# JLink_ARM-OB_Sch.net
KiCad netlist of a schematic drawn in Altium Designer
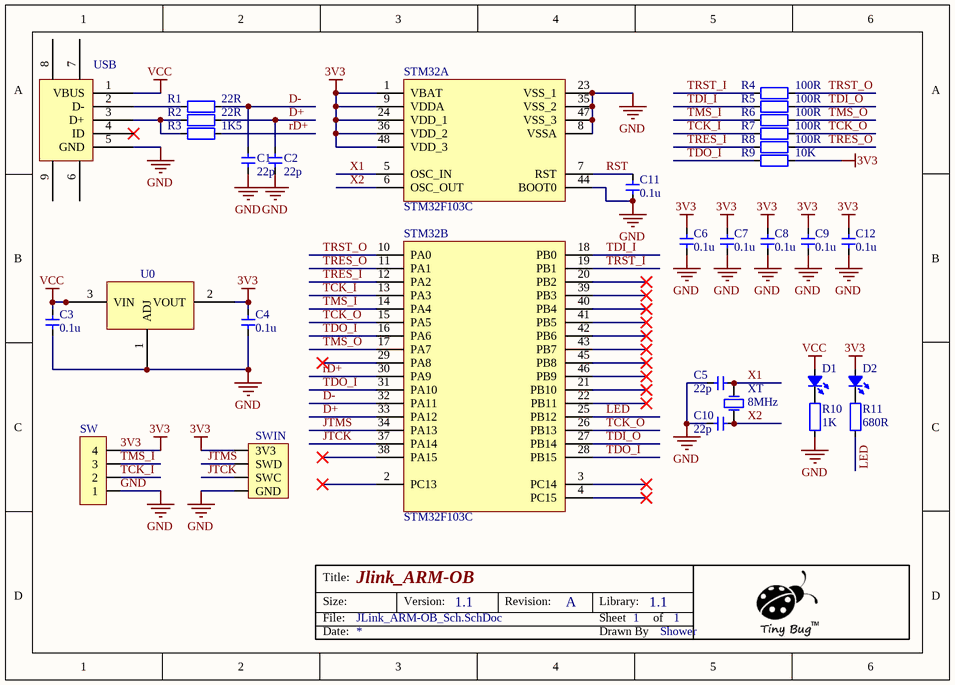
[diagram p0: JLink_ARM-OB_Sch.SchDoc]

(export (version "E")
  (design (tool "Eeschema 10.0.6"))
  (components
    (comp (ref "C1")
      (value "22p")
      (footprint "0603C")
      (description "Capacitor")
      (fields (field (name "Comment") "Cap_0603"))
      (libsource (lib "altium-import") (part "root_1_Cap_0603_"))
    )
    (comp (ref "C2")
      (value "22p")
      (footprint "0603C")
      (description "Capacitor")
      (fields (field (name "Comment") "Cap_0603"))
      (libsource (lib "SCH_Passive") (part "Cap_0603"))
    )
    (comp (ref "C3")
      (value "0.1u")
      (footprint "0603C")
      (description "Capacitor")
      (fields (field (name "Comment") "Cap_0603"))
      (libsource (lib "SCH_Passive") (part "Cap_0603"))
    )
    (comp (ref "C4")
      (value "0.1u")
      (footprint "0603C")
      (description "Capacitor")
      (fields (field (name "Comment") "Cap_0603"))
      (libsource (lib "SCH_Passive") (part "Cap_0603"))
    )
    (comp (ref "C5")
      (value "22p")
      (footprint "0603C")
      (description "Capacitor")
      (fields (field (name "Comment") "Cap_0603"))
      (libsource (lib "SCH_Passive") (part "Cap_0603"))
    )
    (comp (ref "C6")
      (value "0.1u")
      (footprint "0603C")
      (description "Capacitor")
      (fields (field (name "Comment") "Cap_0603"))
      (libsource (lib "SCH_Passive") (part "Cap_0603"))
    )
    (comp (ref "C7")
      (value "0.1u")
      (footprint "0603C")
      (description "Capacitor")
      (fields (field (name "Comment") "Cap_0603"))
      (libsource (lib "SCH_Passive") (part "Cap_0603"))
    )
    (comp (ref "C8")
      (value "0.1u")
      (footprint "0603C")
      (description "Capacitor")
      (fields (field (name "Comment") "Cap_0603"))
      (libsource (lib "SCH_Passive") (part "Cap_0603"))
    )
    (comp (ref "C9")
      (value "0.1u")
      (footprint "0603C")
      (description "Capacitor")
      (fields (field (name "Comment") "Cap_0603"))
      (libsource (lib "SCH_Passive") (part "Cap_0603"))
    )
    (comp (ref "C10")
      (value "22p")
      (footprint "0603C")
      (description "Capacitor")
      (fields (field (name "Comment") "Cap_0603"))
      (libsource (lib "SCH_Passive") (part "Cap_0603"))
    )
    (comp (ref "C11")
      (value "0.1u")
      (footprint "0603C")
      (description "Capacitor")
      (fields (field (name "Comment") "Cap_0603"))
      (libsource (lib "SCH_Passive") (part "Cap_0603"))
    )
    (comp (ref "C12")
      (value "0.1u")
      (footprint "0603C")
      (description "Capacitor")
      (fields (field (name "Comment") "Cap_0603"))
      (libsource (lib "SCH_Passive") (part "Cap_0603"))
    )
    (comp (ref "D1")
      (value "LED_0603")
      (footprint "LED-0603")
      (description "LED")
      (libsource (lib "SCH_Active") (part "LED_0603"))
    )
    (comp (ref "D2")
      (value "LED_0603")
      (footprint "LED-0603")
      (description "LED")
      (libsource (lib "SCH_Active") (part "LED_0603"))
    )
    (comp (ref "R1")
      (value "22R")
      (footprint "0603R")
      (description "Resistor")
      (fields (field (name "Comment") "Res_0603"))
      (libsource (lib "SCH_Passive") (part "Res_0603"))
    )
    (comp (ref "R2")
      (value "22R")
      (footprint "0603R")
      (description "Resistor")
      (fields (field (name "Comment") "Res_0603"))
      (libsource (lib "SCH_Passive") (part "Res_0603"))
    )
    (comp (ref "R3")
      (value "1K5")
      (footprint "0603R")
      (description "Resistor")
      (fields (field (name "Comment") "Res_0603"))
      (libsource (lib "SCH_Passive") (part "Res_0603"))
    )
    (comp (ref "R4")
      (value "100R")
      (footprint "0603R")
      (description "Resistor")
      (fields (field (name "Comment") "Res_0603"))
      (libsource (lib "altium-import") (part "root_0_Res_0603_"))
    )
    (comp (ref "R5")
      (value "100R")
      (footprint "0603R")
      (description "Resistor")
      (fields (field (name "Comment") "Res_0603"))
      (libsource (lib "SCH_Passive") (part "Res_0603"))
    )
    (comp (ref "R6")
      (value "100R")
      (footprint "0603R")
      (description "Resistor")
      (fields (field (name "Comment") "Res_0603"))
      (libsource (lib "SCH_Passive") (part "Res_0603"))
    )
    (comp (ref "R7")
      (value "100R")
      (footprint "0603R")
      (description "Resistor")
      (fields (field (name "Comment") "Res_0603"))
      (libsource (lib "SCH_Passive") (part "Res_0603"))
    )
    (comp (ref "R8")
      (value "100R")
      (footprint "0603R")
      (description "Resistor")
      (fields (field (name "Comment") "Res_0603"))
      (libsource (lib "SCH_Passive") (part "Res_0603"))
    )
    (comp (ref "R9")
      (value "10K")
      (footprint "0603R")
      (description "Resistor")
      (fields (field (name "Comment") "Res_0603"))
      (libsource (lib "SCH_Passive") (part "Res_0603"))
    )
    (comp (ref "R10")
      (value "1K")
      (footprint "0603R")
      (description "Resistor")
      (fields (field (name "Comment") "Res_0603"))
      (libsource (lib "") (part "Res_0603_1"))
    )
    (comp (ref "R11")
      (value "680R")
      (footprint "0603R")
      (description "Resistor")
      (fields (field (name "Comment") "Res_0603"))
      (libsource (lib "") (part "Res_0603_1"))
    )
    (comp (ref "STM32")
      (value "STM32F103C")
      (footprint "LQFP48_N")
      (description "MCU")
      (libsource (lib "SCH_IC") (part "STM32F103C"))
    )
    (comp (ref "SW")
      (value "HDR1X4_90_2.54")
      (footprint "HDR1X4")
      (description "Header")
      (libsource (lib "SCH_Connector") (part "HDR1X4_90_2.54"))
    )
    (comp (ref "SWIN")
      (value "Pad1X4_1.27_SWD")
      (footprint "HDR1X4")
      (description "Header")
      (libsource (lib "SCH_Connector") (part "Pad1X4_1.27_SWD"))
    )
    (comp (ref "U0")
      (value "AMS1117_3.3")
      (footprint "AMS1117_3.3V")
      (libsource (lib "Shower") (part "AMS1117-3.3"))
    )
    (comp (ref "USB") (value "USB_MINI") (footprint "usb_mini") (libsource (lib "Shower") (part "USB_MINI")))
    (comp (ref "XT")
      (value "8MHz")
      (footprint "XTAL")
      (description "Crystal Oscillator")
      (fields (field (name "Comment") "XTAL_5032_2P"))
      (libsource (lib "SCH_Oscillator") (part "XTAL_5032_2P"))
    )
  )
  (nets
    (net (code "1") (name "/D+") (class "Default")
      (node (ref "C2") (pin "2") (pinfunction "2_2") (pintype "passive"))
      (node (ref "R2") (pin "2") (pinfunction "2_2") (pintype "passive"))
      (node (ref "STM32") (pin "33") (pinfunction "PA12_33") (pintype "passive"))
    )
    (net (code "2") (name "/D-") (class "Default")
      (node (ref "C1") (pin "2") (pinfunction "2_2") (pintype "passive"))
      (node (ref "R1") (pin "2") (pinfunction "2_2") (pintype "passive"))
      (node (ref "STM32") (pin "32") (pinfunction "PA11_32") (pintype "passive"))
    )
    (net (code "3") (name "/JTCK") (class "Default")
      (node (ref "STM32") (pin "37") (pinfunction "PA14_37") (pintype "passive"))
      (node (ref "SWIN") (pin "3") (pinfunction "SWC_3") (pintype "passive"))
    )
    (net (code "4") (name "/JTMS") (class "Default")
      (node (ref "STM32") (pin "34") (pinfunction "PA13_34") (pintype "passive"))
      (node (ref "SWIN") (pin "2") (pinfunction "SWD_2") (pintype "passive"))
    )
    (net (code "5") (name "/LED") (class "Default")
      (node (ref "R11") (pin "1") (pinfunction "1_1") (pintype "passive"))
      (node (ref "STM32") (pin "25") (pinfunction "PB12_25") (pintype "passive"))
    )
    (net (code "6") (name "/RST") (class "Default")
      (node (ref "C11") (pin "1") (pinfunction "1_1") (pintype "passive"))
      (node (ref "STM32") (pin "7") (pinfunction "RST_7") (pintype "passive"))
    )
    (net (code "7") (name "/TCK_I") (class "Default")
      (node (ref "R7") (pin "1") (pinfunction "1_1") (pintype "passive"))
      (node (ref "STM32") (pin "13") (pinfunction "PA3_13") (pintype "passive"))
      (node (ref "SW") (pin "2") (pinfunction "2_2") (pintype "passive"))
    )
    (net (code "8") (name "/TCK_O") (class "Default")
      (node (ref "R7") (pin "2") (pinfunction "2_2") (pintype "passive"))
      (node (ref "STM32") (pin "15") (pinfunction "PA5_15") (pintype "passive"))
      (node (ref "STM32") (pin "26") (pinfunction "PB13_26") (pintype "passive"))
    )
    (net (code "9") (name "/TDI_I") (class "Default")
      (node (ref "R5") (pin "1") (pinfunction "1_1") (pintype "passive"))
      (node (ref "STM32") (pin "18") (pinfunction "PB0_18") (pintype "passive"))
    )
    (net (code "10") (name "/TDI_O") (class "Default")
      (node (ref "R5") (pin "2") (pinfunction "2_2") (pintype "passive"))
      (node (ref "STM32") (pin "27") (pinfunction "PB14_27") (pintype "passive"))
    )
    (net (code "11") (name "/TDO_I") (class "Default")
      (node (ref "R9") (pin "1") (pinfunction "1_1") (pintype "passive"))
      (node (ref "STM32") (pin "16") (pinfunction "PA6_16") (pintype "passive"))
      (node (ref "STM32") (pin "28") (pinfunction "PB15_28") (pintype "passive"))
      (node (ref "STM32") (pin "31") (pinfunction "PA10_31") (pintype "passive"))
    )
    (net (code "12") (name "/TMS_I") (class "Default")
      (node (ref "R6") (pin "1") (pinfunction "1_1") (pintype "passive"))
      (node (ref "STM32") (pin "14") (pinfunction "PA4_14") (pintype "passive"))
      (node (ref "SW") (pin "3") (pinfunction "3_3") (pintype "passive"))
    )
    (net (code "13") (name "/TMS_O") (class "Default")
      (node (ref "R6") (pin "2") (pinfunction "2_2") (pintype "passive"))
      (node (ref "STM32") (pin "17") (pinfunction "PA7_17") (pintype "passive"))
    )
    (net (code "14") (name "/TRES_I") (class "Default")
      (node (ref "R8") (pin "1") (pinfunction "1_1") (pintype "passive"))
      (node (ref "STM32") (pin "12") (pinfunction "PA2_12") (pintype "passive"))
    )
    (net (code "15") (name "/TRES_O") (class "Default")
      (node (ref "R8") (pin "2") (pinfunction "2_2") (pintype "passive"))
      (node (ref "STM32") (pin "11") (pinfunction "PA1_11") (pintype "passive"))
    )
    (net (code "16") (name "/TRST_I") (class "Default")
      (node (ref "R4") (pin "1") (pinfunction "1_1") (pintype "passive"))
      (node (ref "STM32") (pin "19") (pinfunction "PB1_19") (pintype "passive"))
    )
    (net (code "17") (name "/TRST_O") (class "Default")
      (node (ref "R4") (pin "2") (pinfunction "2_2") (pintype "passive"))
      (node (ref "STM32") (pin "10") (pinfunction "PA0_10") (pintype "passive"))
    )
    (net (code "18") (name "/X1") (class "Default")
      (node (ref "C5") (pin "1") (pinfunction "1_1") (pintype "passive"))
      (node (ref "STM32") (pin "5") (pinfunction "OSC_IN_5") (pintype "passive"))
      (node (ref "XT") (pin "2") (pinfunction "OSC2_2") (pintype "passive"))
    )
    (net (code "19") (name "/X2") (class "Default")
      (node (ref "C10") (pin "1") (pinfunction "1_1") (pintype "passive"))
      (node (ref "STM32") (pin "6") (pinfunction "OSC_OUT_6") (pintype "passive"))
      (node (ref "XT") (pin "1") (pinfunction "OSC1_1") (pintype "passive"))
    )
    (net (code "20") (name "/rD+") (class "Default")
      (node (ref "R3") (pin "2") (pinfunction "2_2") (pintype "passive"))
      (node (ref "STM32") (pin "30") (pinfunction "PA9_30") (pintype "passive"))
    )
    (net (code "21") (name "3V3") (class "Default")
      (node (ref "C12") (pin "1") (pinfunction "1_1") (pintype "passive"))
      (node (ref "C4") (pin "2") (pinfunction "2_2") (pintype "passive"))
      (node (ref "C6") (pin "1") (pinfunction "1_1") (pintype "passive"))
      (node (ref "C7") (pin "1") (pinfunction "1_1") (pintype "passive"))
      (node (ref "C8") (pin "1") (pinfunction "1_1") (pintype "passive"))
      (node (ref "C9") (pin "1") (pinfunction "1_1") (pintype "passive"))
      (node (ref "D2") (pin "1") (pinfunction "A_1") (pintype "passive"))
      (node (ref "R9") (pin "2") (pinfunction "2_2") (pintype "passive"))
      (node (ref "STM32") (pin "1") (pinfunction "VBAT_1") (pintype "passive"))
      (node (ref "STM32") (pin "24") (pinfunction "VDD_1_24") (pintype "passive"))
      (node (ref "STM32") (pin "36") (pinfunction "VDD_2_36") (pintype "passive"))
      (node (ref "STM32") (pin "48") (pinfunction "VDD_3_48") (pintype "passive"))
      (node (ref "STM32") (pin "9") (pinfunction "VDDA_9") (pintype "passive"))
      (node (ref "SW") (pin "4") (pinfunction "4_4") (pintype "passive"))
      (node (ref "SWIN") (pin "1") (pinfunction "3V3_1") (pintype "passive"))
      (node (ref "U0") (pin "2") (pinfunction "VOUT_2") (pintype "passive"))
    )
    (net (code "22") (name "GND") (class "Default")
      (node (ref "C1") (pin "1") (pinfunction "1_1") (pintype "passive"))
      (node (ref "C10") (pin "2") (pinfunction "2_2") (pintype "passive"))
      (node (ref "C11") (pin "2") (pinfunction "2_2") (pintype "passive"))
      (node (ref "C12") (pin "2") (pinfunction "2_2") (pintype "passive"))
      (node (ref "C2") (pin "1") (pinfunction "1_1") (pintype "passive"))
      (node (ref "C3") (pin "1") (pinfunction "1_1") (pintype "passive"))
      (node (ref "C4") (pin "1") (pinfunction "1_1") (pintype "passive"))
      (node (ref "C5") (pin "2") (pinfunction "2_2") (pintype "passive"))
      (node (ref "C6") (pin "2") (pinfunction "2_2") (pintype "passive"))
      (node (ref "C7") (pin "2") (pinfunction "2_2") (pintype "passive"))
      (node (ref "C8") (pin "2") (pinfunction "2_2") (pintype "passive"))
      (node (ref "C9") (pin "2") (pinfunction "2_2") (pintype "passive"))
      (node (ref "R10") (pin "1") (pinfunction "1_1") (pintype "passive"))
      (node (ref "STM32") (pin "23") (pinfunction "VSS_1_23") (pintype "passive"))
      (node (ref "STM32") (pin "35") (pinfunction "VSS_2_35") (pintype "passive"))
      (node (ref "STM32") (pin "44") (pinfunction "BOOT0_44") (pintype "passive"))
      (node (ref "STM32") (pin "47") (pinfunction "VSS_3_47") (pintype "passive"))
      (node (ref "STM32") (pin "8") (pinfunction "VSSA_8") (pintype "passive"))
      (node (ref "SW") (pin "1") (pinfunction "1_1") (pintype "passive"))
      (node (ref "SWIN") (pin "4") (pinfunction "GND_4") (pintype "passive"))
      (node (ref "U0") (pin "1") (pinfunction "ADJ_1") (pintype "passive"))
      (node (ref "USB") (pin "5") (pinfunction "GND_5") (pintype "passive"))
    )
    (net (code "23") (name "Net-(D1-K)") (class "Default")
      (node (ref "D1") (pin "2") (pinfunction "K_2") (pintype "passive"))
      (node (ref "R10") (pin "2") (pinfunction "2_2") (pintype "passive"))
    )
    (net (code "24") (name "Net-(D2-K)") (class "Default")
      (node (ref "D2") (pin "2") (pinfunction "K_2") (pintype "passive"))
      (node (ref "R11") (pin "2") (pinfunction "2_2") (pintype "passive"))
    )
    (net (code "25") (name "Net-(USB-D+)") (class "Default")
      (node (ref "R2") (pin "1") (pinfunction "1_1") (pintype "passive"))
      (node (ref "R3") (pin "1") (pinfunction "1_1") (pintype "passive"))
      (node (ref "USB") (pin "3") (pinfunction "D+_3") (pintype "passive"))
    )
    (net (code "26") (name "Net-(USB-D-)") (class "Default")
      (node (ref "R1") (pin "1") (pinfunction "1_1") (pintype "passive"))
      (node (ref "USB") (pin "2") (pinfunction "D-_2") (pintype "passive"))
    )
    (net (code "27") (name "VCC") (class "Default")
      (node (ref "C3") (pin "2") (pinfunction "2_2") (pintype "passive"))
      (node (ref "D1") (pin "1") (pinfunction "A_1") (pintype "passive"))
      (node (ref "U0") (pin "3") (pinfunction "VIN_3") (pintype "passive"))
      (node (ref "USB") (pin "1") (pinfunction "VBUS_1") (pintype "passive"))
    )
    (net (code "28") (name "unconnected-(STM32B-PA8-Pad29)") (class "Default")
      (node (ref "STM32") (pin "29") (pinfunction "PA8_29") (pintype "passive+no_connect"))
    )
    (net (code "29") (name "unconnected-(STM32B-PA15-Pad38)") (class "Default")
      (node (ref "STM32") (pin "38") (pinfunction "PA15_38") (pintype "passive+no_connect"))
    )
    (net (code "30") (name "unconnected-(STM32B-PB2-Pad20)") (class "Default")
      (node (ref "STM32") (pin "20") (pinfunction "PB2_20") (pintype "passive+no_connect"))
    )
    (net (code "31") (name "unconnected-(STM32B-PB3-Pad39)") (class "Default")
      (node (ref "STM32") (pin "39") (pinfunction "PB3_39") (pintype "passive+no_connect"))
    )
    (net (code "32") (name "unconnected-(STM32B-PB4-Pad40)") (class "Default")
      (node (ref "STM32") (pin "40") (pinfunction "PB4_40") (pintype "passive+no_connect"))
    )
    (net (code "33") (name "unconnected-(STM32B-PB5-Pad41)") (class "Default")
      (node (ref "STM32") (pin "41") (pinfunction "PB5_41") (pintype "passive+no_connect"))
    )
    (net (code "34") (name "unconnected-(STM32B-PB6-Pad42)") (class "Default")
      (node (ref "STM32") (pin "42") (pinfunction "PB6_42") (pintype "passive+no_connect"))
    )
    (net (code "35") (name "unconnected-(STM32B-PB7-Pad43)") (class "Default")
      (node (ref "STM32") (pin "43") (pinfunction "PB7_43") (pintype "passive+no_connect"))
    )
    (net (code "36") (name "unconnected-(STM32B-PB8-Pad45)") (class "Default")
      (node (ref "STM32") (pin "45") (pinfunction "PB8_45") (pintype "passive+no_connect"))
    )
    (net (code "37") (name "unconnected-(STM32B-PB9-Pad46)") (class "Default")
      (node (ref "STM32") (pin "46") (pinfunction "PB9_46") (pintype "passive+no_connect"))
    )
    (net (code "38") (name "unconnected-(STM32B-PB10-Pad21)") (class "Default")
      (node (ref "STM32") (pin "21") (pinfunction "PB10_21") (pintype "passive+no_connect"))
    )
    (net (code "39") (name "unconnected-(STM32B-PB11-Pad22)") (class "Default")
      (node (ref "STM32") (pin "22") (pinfunction "PB11_22") (pintype "passive+no_connect"))
    )
    (net (code "40") (name "unconnected-(STM32B-PC13-Pad2)") (class "Default")
      (node (ref "STM32") (pin "2") (pinfunction "PC13_2") (pintype "passive+no_connect"))
    )
    (net (code "41") (name "unconnected-(STM32B-PC14-Pad3)") (class "Default")
      (node (ref "STM32") (pin "3") (pinfunction "PC14_3") (pintype "passive+no_connect"))
    )
    (net (code "42") (name "unconnected-(STM32B-PC15-Pad4)") (class "Default")
      (node (ref "STM32") (pin "4") (pinfunction "PC15_4") (pintype "passive+no_connect"))
    )
    (net (code "43") (name "unconnected-(USB-ID-Pad4)") (class "Default")
      (node (ref "USB") (pin "4") (pinfunction "ID_4") (pintype "passive+no_connect"))
    )
    (net (code "44") (name "unconnected-(USB-Pad6)") (class "Default")
      (node (ref "USB") (pin "6") (pinfunction "6_6") (pintype "passive"))
    )
    (net (code "45") (name "unconnected-(USB-Pad7)") (class "Default")
      (node (ref "USB") (pin "7") (pinfunction "7_7") (pintype "passive"))
    )
    (net (code "46") (name "unconnected-(USB-Pad8)") (class "Default")
      (node (ref "USB") (pin "8") (pinfunction "8_8") (pintype "passive"))
    )
    (net (code "47") (name "unconnected-(USB-Pad9)") (class "Default")
      (node (ref "USB") (pin "9") (pinfunction "9_9") (pintype "passive"))
    )
  )
)
